# led_remote.net
KiCad netlist of a schematic drawn in EAGLE
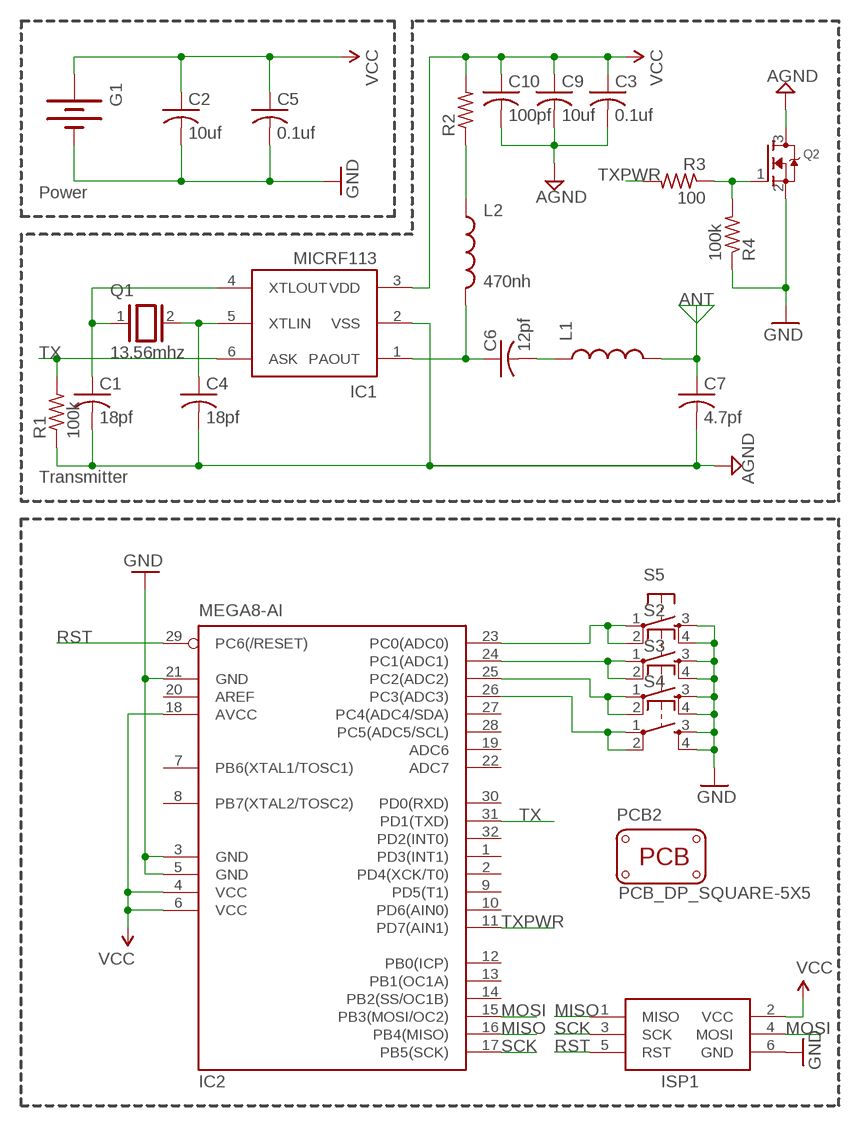
[diagram p0: schematic, sheet 1]

(export (version "E")
  (design (tool "Eeschema 10.0.6"))
  (components
    (comp (ref "C1")
      (value "18pf")
      (footprint "eagle-import:C1206")
      (libsource (lib "eagle-import") (part "C-USC1206"))
    )
    (comp (ref "C2")
      (value "10uf")
      (footprint "eagle-import:C1206")
      (libsource (lib "eagle-import") (part "C-USC1206"))
    )
    (comp (ref "C3")
      (value "0.1uf")
      (footprint "eagle-import:C1206")
      (libsource (lib "eagle-import") (part "C-USC1206"))
    )
    (comp (ref "C4")
      (value "18pf")
      (footprint "eagle-import:C1206")
      (libsource (lib "eagle-import") (part "C-USC1206"))
    )
    (comp (ref "C5")
      (value "0.1uf")
      (footprint "eagle-import:C1206")
      (libsource (lib "eagle-import") (part "C-USC1206"))
    )
    (comp (ref "C6")
      (value "12pf")
      (footprint "eagle-import:C1206")
      (libsource (lib "eagle-import") (part "C-USC1206"))
    )
    (comp (ref "C7")
      (value "4.7pf")
      (footprint "eagle-import:C1206")
      (libsource (lib "eagle-import") (part "C-USC1206"))
    )
    (comp (ref "C9")
      (value "10uf")
      (footprint "eagle-import:C1206")
      (libsource (lib "eagle-import") (part "C-USC1206"))
    )
    (comp (ref "C10")
      (value "100pf")
      (footprint "eagle-import:C1206")
      (libsource (lib "eagle-import") (part "C-USC1206"))
    )
    (comp (ref "G1")
      (value "BATTERY20SMD")
      (footprint "eagle-import:BATTCON_20MM")
      (libsource (lib "eagle-import") (part "BATTERY20SMD"))
    )
    (comp (ref "IC1")
      (value "MICRF113")
      (footprint "eagle-import:SOT23-6")
      (libsource (lib "eagle-import") (part "MICRF113"))
    )
    (comp (ref "IC2")
      (value "MEGA8-AI")
      (footprint "eagle-import:TQFP32-08")
      (fields (field (name "MPN") "ATMEGA8-16AU"))
      (libsource (lib "eagle-import") (part "MEGA8-AI"))
    )
    (comp (ref "ISP1")
      (value "AVRISP-6")
      (footprint "eagle-import:AVRISP")
      (libsource (lib "eagle-import") (part "AVRISP-6"))
    )
    (comp (ref "L1")
      (value "INDUCTOR1210")
      (footprint "eagle-import:1210")
      (libsource (lib "eagle-import") (part "INDUCTOR1210"))
    )
    (comp (ref "L2")
      (value "470nh")
      (footprint "eagle-import:1210")
      (libsource (lib "eagle-import") (part "INDUCTOR1210"))
    )
    (comp (ref "PCB2")
      (value "PCB_DP_SQUARE-5X5")
      (footprint "eagle-import:DP5050_V1")
      (libsource (lib "eagle-import") (part "PCB_DP_SQUARE-5X5"))
    )
    (comp (ref "Q1")
      (value "13.56mhz")
      (footprint "eagle-import:QS")
      (libsource (lib "eagle-import") (part "XTAL/S"))
    )
    (comp (ref "Q2")
      (value "MOSFET-NREFLOW")
      (footprint "eagle-import:SOT23")
      (libsource (lib "eagle-import") (part "MOSFET-NREFLOW"))
    )
    (comp (ref "R1")
      (value "100k")
      (footprint "eagle-import:R1206")
      (libsource (lib "eagle-import") (part "R-US_R1206"))
    )
    (comp (ref "R2")
      (value "R-US_R1206")
      (footprint "eagle-import:R1206")
      (libsource (lib "eagle-import") (part "R-US_R1206"))
    )
    (comp (ref "R3")
      (value "100")
      (footprint "eagle-import:R1206")
      (libsource (lib "eagle-import") (part "R-US_R1206"))
    )
    (comp (ref "R4")
      (value "100k")
      (footprint "eagle-import:R1206")
      (libsource (lib "eagle-import") (part "R-US_R1206"))
    )
    (comp (ref "S2")
      (value "TAC_SWITCHSMD")
      (footprint "eagle-import:TACTILE_SWITCH_SMD")
      (libsource (lib "eagle-import") (part "TAC_SWITCHSMD"))
    )
    (comp (ref "S3")
      (value "TAC_SWITCHSMD")
      (footprint "eagle-import:TACTILE_SWITCH_SMD")
      (libsource (lib "eagle-import") (part "TAC_SWITCHSMD"))
    )
    (comp (ref "S4")
      (value "TAC_SWITCHSMD")
      (footprint "eagle-import:TACTILE_SWITCH_SMD")
      (libsource (lib "eagle-import") (part "TAC_SWITCHSMD"))
    )
    (comp (ref "S5")
      (value "TAC_SWITCHSMD")
      (footprint "eagle-import:TACTILE_SWITCH_SMD")
      (libsource (lib "eagle-import") (part "TAC_SWITCHSMD"))
    )
  )
  (nets
    (net (code "1") (name "/ANT") (class "Default")
      (node (ref "C7") (pin "1") (pinfunction "1_1") (pintype "passive"))
      (node (ref "L1") (pin "2") (pinfunction "2_2") (pintype "passive"))
    )
    (net (code "2") (name "/MISO") (class "Default")
      (node (ref "IC2") (pin "16") (pinfunction "PB4(MISO)_16") (pintype "bidirectional"))
      (node (ref "ISP1") (pin "1") (pinfunction "MISO_1") (pintype "input"))
    )
    (net (code "3") (name "/MOSI") (class "Default")
      (node (ref "IC2") (pin "15") (pinfunction "PB3(MOSI/OC2)_15") (pintype "bidirectional"))
      (node (ref "ISP1") (pin "4") (pinfunction "MOSI_4") (pintype "output"))
    )
    (net (code "4") (name "/RST") (class "Default")
      (node (ref "IC2") (pin "29") (pinfunction "PC6(/RESET)_29") (pintype "bidirectional"))
      (node (ref "ISP1") (pin "5") (pinfunction "RST_5") (pintype "output"))
    )
    (net (code "5") (name "/SCK") (class "Default")
      (node (ref "IC2") (pin "17") (pinfunction "PB5(SCK)_17") (pintype "bidirectional"))
      (node (ref "ISP1") (pin "3") (pinfunction "SCK_3") (pintype "output"))
    )
    (net (code "6") (name "/TX") (class "Default")
      (node (ref "IC1") (pin "6") (pinfunction "ASK_6") (pintype "bidirectional"))
      (node (ref "IC2") (pin "31") (pinfunction "PD1(TXD)_31") (pintype "bidirectional"))
      (node (ref "R1") (pin "2") (pinfunction "2_2") (pintype "passive"))
    )
    (net (code "7") (name "/TXPWR") (class "Default")
      (node (ref "IC2") (pin "11") (pinfunction "PD7(AIN1)_11") (pintype "bidirectional"))
      (node (ref "R3") (pin "2") (pinfunction "2_2") (pintype "passive"))
    )
    (net (code "8") (name "AGND") (class "Default")
      (node (ref "C1") (pin "2") (pinfunction "2_2") (pintype "passive"))
      (node (ref "C10") (pin "2") (pinfunction "2_2") (pintype "passive"))
      (node (ref "C3") (pin "2") (pinfunction "2_2") (pintype "passive"))
      (node (ref "C4") (pin "2") (pinfunction "2_2") (pintype "passive"))
      (node (ref "C7") (pin "2") (pinfunction "2_2") (pintype "passive"))
      (node (ref "C9") (pin "2") (pinfunction "2_2") (pintype "passive"))
      (node (ref "IC1") (pin "2") (pinfunction "VSS_2") (pintype "bidirectional"))
      (node (ref "Q2") (pin "3") (pinfunction "D_3") (pintype "bidirectional"))
      (node (ref "R1") (pin "1") (pinfunction "1_1") (pintype "passive"))
    )
    (net (code "9") (name "GND") (class "Default")
      (node (ref "C2") (pin "2") (pinfunction "2_2") (pintype "passive"))
      (node (ref "C5") (pin "2") (pinfunction "2_2") (pintype "passive"))
      (node (ref "G1") (pin "2") (pinfunction "-_2") (pintype "power_in"))
      (node (ref "IC2") (pin "21") (pinfunction "GND_21") (pintype "power_in"))
      (node (ref "IC2") (pin "3") (pinfunction "GND_3") (pintype "power_in"))
      (node (ref "IC2") (pin "5") (pinfunction "GND_5") (pintype "power_in"))
      (node (ref "ISP1") (pin "6") (pinfunction "GND_6") (pintype "power_in"))
      (node (ref "Q2") (pin "2") (pinfunction "S_2") (pintype "bidirectional"))
      (node (ref "R4") (pin "1") (pinfunction "1_1") (pintype "passive"))
      (node (ref "S2") (pin "3") (pinfunction "3_3") (pintype "passive"))
      (node (ref "S2") (pin "4") (pinfunction "4_4") (pintype "passive"))
      (node (ref "S3") (pin "3") (pinfunction "3_3") (pintype "passive"))
      (node (ref "S3") (pin "4") (pinfunction "4_4") (pintype "passive"))
      (node (ref "S4") (pin "3") (pinfunction "3_3") (pintype "passive"))
      (node (ref "S4") (pin "4") (pinfunction "4_4") (pintype "passive"))
      (node (ref "S5") (pin "3") (pinfunction "3_3") (pintype "passive"))
      (node (ref "S5") (pin "4") (pinfunction "4_4") (pintype "passive"))
    )
    (net (code "10") (name "Net-(C6-Pad2)") (class "Default")
      (node (ref "C6") (pin "2") (pinfunction "2_2") (pintype "passive"))
      (node (ref "L1") (pin "1") (pinfunction "1_1") (pintype "passive"))
    )
    (net (code "11") (name "Net-(IC1-PAOUT)") (class "Default")
      (node (ref "C6") (pin "1") (pinfunction "1_1") (pintype "passive"))
      (node (ref "IC1") (pin "1") (pinfunction "PAOUT_1") (pintype "bidirectional"))
      (node (ref "L2") (pin "2") (pinfunction "2_2") (pintype "passive"))
    )
    (net (code "12") (name "Net-(IC1-XTLIN)") (class "Default")
      (node (ref "C4") (pin "1") (pinfunction "1_1") (pintype "passive"))
      (node (ref "IC1") (pin "5") (pinfunction "XTLIN_5") (pintype "bidirectional"))
      (node (ref "Q1") (pin "2") (pinfunction "2_2") (pintype "passive"))
    )
    (net (code "13") (name "Net-(IC1-XTLOUT)") (class "Default")
      (node (ref "C1") (pin "1") (pinfunction "1_1") (pintype "passive"))
      (node (ref "IC1") (pin "4") (pinfunction "XTLOUT_4") (pintype "bidirectional"))
      (node (ref "Q1") (pin "1") (pinfunction "1_1") (pintype "passive"))
    )
    (net (code "14") (name "Net-(IC2-PC0(ADC0))") (class "Default")
      (node (ref "IC2") (pin "23") (pinfunction "PC0(ADC0)_23") (pintype "bidirectional"))
      (node (ref "S5") (pin "1") (pinfunction "1_1") (pintype "passive"))
      (node (ref "S5") (pin "2") (pinfunction "2_2") (pintype "passive"))
    )
    (net (code "15") (name "Net-(IC2-PC1(ADC1))") (class "Default")
      (node (ref "IC2") (pin "24") (pinfunction "PC1(ADC1)_24") (pintype "bidirectional"))
      (node (ref "S2") (pin "1") (pinfunction "1_1") (pintype "passive"))
      (node (ref "S2") (pin "2") (pinfunction "2_2") (pintype "passive"))
    )
    (net (code "16") (name "Net-(IC2-PC2(ADC2))") (class "Default")
      (node (ref "IC2") (pin "25") (pinfunction "PC2(ADC2)_25") (pintype "bidirectional"))
      (node (ref "S3") (pin "1") (pinfunction "1_1") (pintype "passive"))
      (node (ref "S3") (pin "2") (pinfunction "2_2") (pintype "passive"))
    )
    (net (code "17") (name "Net-(IC2-PC3(ADC3))") (class "Default")
      (node (ref "IC2") (pin "26") (pinfunction "PC3(ADC3)_26") (pintype "bidirectional"))
      (node (ref "S4") (pin "1") (pinfunction "1_1") (pintype "passive"))
      (node (ref "S4") (pin "2") (pinfunction "2_2") (pintype "passive"))
    )
    (net (code "18") (name "Net-(L2-Pad1)") (class "Default")
      (node (ref "L2") (pin "1") (pinfunction "1_1") (pintype "passive"))
      (node (ref "R2") (pin "1") (pinfunction "1_1") (pintype "passive"))
    )
    (net (code "19") (name "Net-(Q2-G)") (class "Default")
      (node (ref "Q2") (pin "1") (pinfunction "G_1") (pintype "bidirectional"))
      (node (ref "R3") (pin "1") (pinfunction "1_1") (pintype "passive"))
      (node (ref "R4") (pin "2") (pinfunction "2_2") (pintype "passive"))
    )
    (net (code "20") (name "VCC") (class "Default")
      (node (ref "C10") (pin "1") (pinfunction "1_1") (pintype "passive"))
      (node (ref "C2") (pin "1") (pinfunction "1_1") (pintype "passive"))
      (node (ref "C3") (pin "1") (pinfunction "1_1") (pintype "passive"))
      (node (ref "C5") (pin "1") (pinfunction "1_1") (pintype "passive"))
      (node (ref "C9") (pin "1") (pinfunction "1_1") (pintype "passive"))
      (node (ref "G1") (pin "1") (pinfunction "+_1") (pintype "power_in"))
      (node (ref "IC1") (pin "3") (pinfunction "VDD_3") (pintype "bidirectional"))
      (node (ref "IC2") (pin "18") (pinfunction "AVCC_18") (pintype "power_in"))
      (node (ref "IC2") (pin "4") (pinfunction "VCC_4") (pintype "power_in"))
      (node (ref "IC2") (pin "6") (pinfunction "VCC_6") (pintype "power_in"))
      (node (ref "ISP1") (pin "2") (pinfunction "VCC_2") (pintype "power_in"))
      (node (ref "R2") (pin "2") (pinfunction "2_2") (pintype "passive"))
    )
    (net (code "21") (name "unconnected-(IC2-ADC6-Pad19)") (class "Default")
      (node (ref "IC2") (pin "19") (pinfunction "ADC6_19") (pintype "bidirectional"))
    )
    (net (code "22") (name "unconnected-(IC2-ADC7-Pad22)") (class "Default")
      (node (ref "IC2") (pin "22") (pinfunction "ADC7_22") (pintype "bidirectional"))
    )
    (net (code "23") (name "unconnected-(IC2-AREF-Pad20)") (class "Default")
      (node (ref "IC2") (pin "20") (pinfunction "AREF_20") (pintype "passive"))
    )
    (net (code "24") (name "unconnected-(IC2-PB0(ICP)-Pad12)") (class "Default")
      (node (ref "IC2") (pin "12") (pinfunction "PB0(ICP)_12") (pintype "bidirectional"))
    )
    (net (code "25") (name "unconnected-(IC2-PB1(OC1A)-Pad13)") (class "Default")
      (node (ref "IC2") (pin "13") (pinfunction "PB1(OC1A)_13") (pintype "bidirectional"))
    )
    (net (code "26") (name "unconnected-(IC2-PB2(SS{slash}OC1B)-Pad14)") (class "Default")
      (node (ref "IC2") (pin "14") (pinfunction "PB2(SS/OC1B)_14") (pintype "bidirectional"))
    )
    (net (code "27") (name "unconnected-(IC2-PB6(XTAL1{slash}TOSC1)-Pad7)") (class "Default")
      (node (ref "IC2") (pin "7") (pinfunction "PB6(XTAL1/TOSC1)_7") (pintype "bidirectional"))
    )
    (net (code "28") (name "unconnected-(IC2-PB7(XTAL2{slash}TOSC2)-Pad8)") (class "Default")
      (node (ref "IC2") (pin "8") (pinfunction "PB7(XTAL2/TOSC2)_8") (pintype "bidirectional"))
    )
    (net (code "29") (name "unconnected-(IC2-PC4(ADC4{slash}SDA)-Pad27)") (class "Default")
      (node (ref "IC2") (pin "27") (pinfunction "PC4(ADC4/SDA)_27") (pintype "bidirectional"))
    )
    (net (code "30") (name "unconnected-(IC2-PC5(ADC5{slash}SCL)-Pad28)") (class "Default")
      (node (ref "IC2") (pin "28") (pinfunction "PC5(ADC5/SCL)_28") (pintype "bidirectional"))
    )
    (net (code "31") (name "unconnected-(IC2-PD0(RXD)-Pad30)") (class "Default")
      (node (ref "IC2") (pin "30") (pinfunction "PD0(RXD)_30") (pintype "bidirectional"))
    )
    (net (code "32") (name "unconnected-(IC2-PD2(INT0)-Pad32)") (class "Default")
      (node (ref "IC2") (pin "32") (pinfunction "PD2(INT0)_32") (pintype "bidirectional"))
    )
    (net (code "33") (name "unconnected-(IC2-PD3(INT1)-Pad1)") (class "Default")
      (node (ref "IC2") (pin "1") (pinfunction "PD3(INT1)_1") (pintype "bidirectional"))
    )
    (net (code "34") (name "unconnected-(IC2-PD4(XCK{slash}T0)-Pad2)") (class "Default")
      (node (ref "IC2") (pin "2") (pinfunction "PD4(XCK/T0)_2") (pintype "bidirectional"))
    )
    (net (code "35") (name "unconnected-(IC2-PD5(T1)-Pad9)") (class "Default")
      (node (ref "IC2") (pin "9") (pinfunction "PD5(T1)_9") (pintype "bidirectional"))
    )
    (net (code "36") (name "unconnected-(IC2-PD6(AIN0)-Pad10)") (class "Default")
      (node (ref "IC2") (pin "10") (pinfunction "PD6(AIN0)_10") (pintype "bidirectional"))
    )
  )
)
